# control_board-mixed.net
KiCad netlist of a schematic drawn in EAGLE
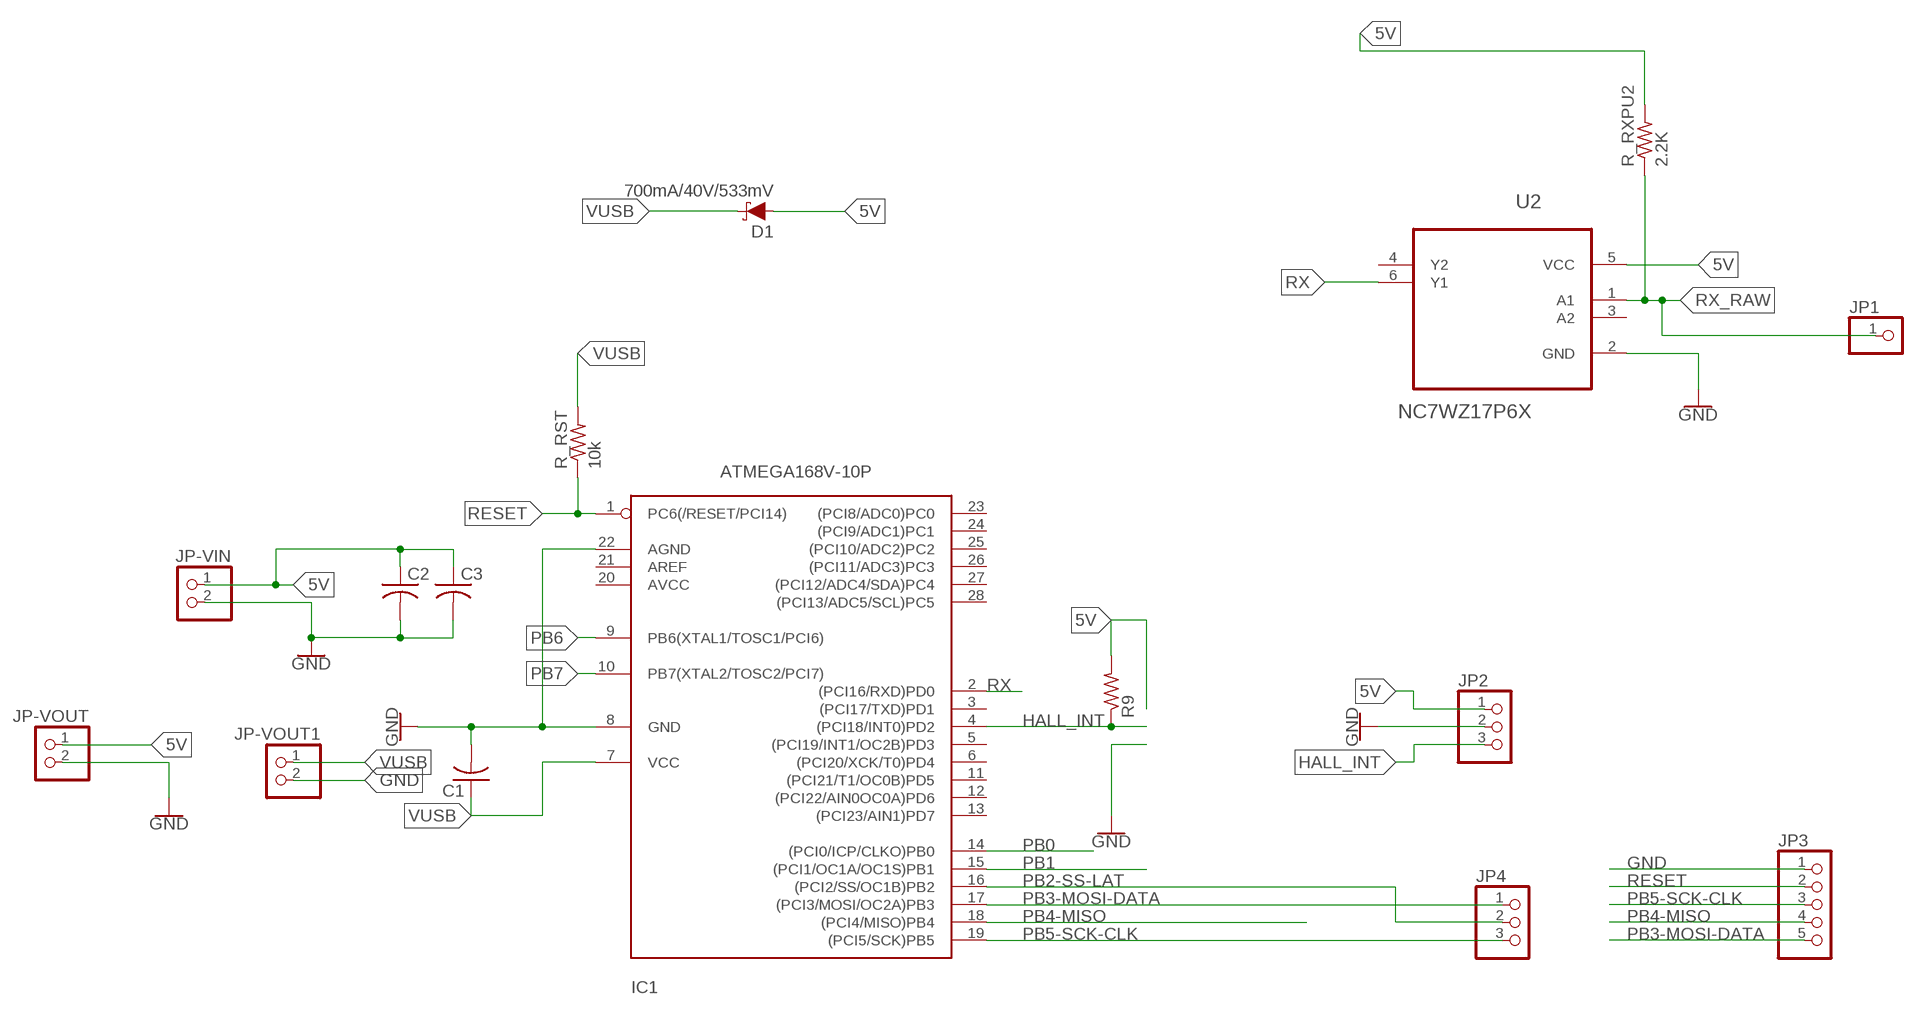
[diagram p0: schematic, sheet 1]

(export (version "E")
  (design (tool "Eeschema 10.0.6"))
  (components
    (comp (ref "C1")
      (value "C-US025-030X050")
      (footprint "eagle-import:C025-030X050")
      (libsource (lib "eagle-import") (part "C-US025-030X050"))
    )
    (comp (ref "C2")
      (value "C-US025-060X050")
      (footprint "eagle-import:C025-060X050")
      (libsource (lib "eagle-import") (part "C-US025-060X050"))
    )
    (comp (ref "C3")
      (value "C-US025-060X050")
      (footprint "eagle-import:C025-060X050")
      (libsource (lib "eagle-import") (part "C-US025-060X050"))
    )
    (comp (ref "D1")
      (value "700mA/40V/533mV")
      (footprint "eagle-import:SOT23-3")
      (libsource (lib "eagle-import") (part "DIODE-SCHOTTKY-ZLLS500"))
    )
    (comp (ref "IC1")
      (value "ATMEGA168V-10P")
      (footprint "eagle-import:DIL28-3")
      (libsource (lib "eagle-import") (part "ATMEGA168PV-10"))
    )
    (comp (ref "JP-VIN")
      (value "PINHD-1X2")
      (footprint "eagle-import:1X02")
      (libsource (lib "eagle-import") (part "PINHD-1X2"))
    )
    (comp (ref "JP-VOUT")
      (value "PINHD-1X2")
      (footprint "eagle-import:1X02")
      (libsource (lib "eagle-import") (part "PINHD-1X2"))
    )
    (comp (ref "JP-VOUT1")
      (value "PINHD-1X2")
      (footprint "eagle-import:1X02")
      (libsource (lib "eagle-import") (part "PINHD-1X2"))
    )
    (comp (ref "JP1")
      (value "PINHD-1X1")
      (footprint "eagle-import:1X01")
      (libsource (lib "eagle-import") (part "PINHD-1X1"))
    )
    (comp (ref "JP2")
      (value "PINHD-1X3")
      (footprint "eagle-import:1X03")
      (libsource (lib "eagle-import") (part "PINHD-1X3"))
    )
    (comp (ref "JP3")
      (value "PINHD-1X5")
      (footprint "eagle-import:1X05")
      (libsource (lib "eagle-import") (part "PINHD-1X5"))
    )
    (comp (ref "JP4")
      (value "PINHD-1X3")
      (footprint "eagle-import:1X03")
      (libsource (lib "eagle-import") (part "PINHD-1X3"))
    )
    (comp (ref "R9")
      (value "R-US_0207/7")
      (footprint "eagle-import:0207_7")
      (libsource (lib "eagle-import") (part "R-US_0207/7"))
    )
    (comp (ref "R_RST")
      (value "10k")
      (footprint "eagle-import:R0603")
      (libsource (lib "eagle-import") (part "R-US_R0603"))
    )
    (comp (ref "R_RXPU2")
      (value "2.2K")
      (footprint "eagle-import:R0603")
      (libsource (lib "eagle-import") (part "R-US_R0603"))
    )
    (comp (ref "U2")
      (value "NC7WZ17P6X")
      (footprint "eagle-import:SOT65P210X110-6N")
      (fields (field (name "MF") "Fairchild Semiconductor"))
      (libsource (lib "eagle-import") (part "NC7WZ17P6X"))
    )
  )
  (nets
    (net (code "1") (name "/PB0") (class "Default")
      (node (ref "IC1") (pin "14") (pinfunction "(PCI0/ICP/CLKO)PB0_14") (pintype "bidirectional"))
    )
    (net (code "2") (name "/PB1") (class "Default")
      (node (ref "IC1") (pin "15") (pinfunction "(PCI1/OC1A/OC1S)PB1_15") (pintype "bidirectional"))
    )
    (net (code "3") (name "/PB2-SS-LAT") (class "Default")
      (node (ref "IC1") (pin "16") (pinfunction "(PCI2/SS/OC1B)PB2_16") (pintype "bidirectional"))
      (node (ref "JP4") (pin "2") (pinfunction "2_2") (pintype "passive"))
    )
    (net (code "4") (name "/PB3-MOSI-DATA") (class "Default")
      (node (ref "IC1") (pin "17") (pinfunction "(PCI3/MOSI/OC2A)PB3_17") (pintype "bidirectional"))
      (node (ref "JP3") (pin "5") (pinfunction "5_5") (pintype "passive"))
      (node (ref "JP4") (pin "1") (pinfunction "1_1") (pintype "passive"))
    )
    (net (code "5") (name "/PB4-MISO") (class "Default")
      (node (ref "IC1") (pin "18") (pinfunction "(PCI4/MISO)PB4_18") (pintype "bidirectional"))
      (node (ref "JP3") (pin "4") (pinfunction "4_4") (pintype "passive"))
    )
    (net (code "6") (name "/PB5-SCK-CLK") (class "Default")
      (node (ref "IC1") (pin "19") (pinfunction "(PCI5/SCK)PB5_19") (pintype "bidirectional"))
      (node (ref "JP3") (pin "3") (pinfunction "3_3") (pintype "passive"))
      (node (ref "JP4") (pin "3") (pinfunction "3_3") (pintype "passive"))
    )
    (net (code "7") (name "5V") (class "Default")
      (node (ref "C2") (pin "1") (pinfunction "1_1") (pintype "passive"))
      (node (ref "C3") (pin "1") (pinfunction "1_1") (pintype "passive"))
      (node (ref "D1") (pin "1") (pinfunction "A_1") (pintype "passive"))
      (node (ref "JP-VIN") (pin "1") (pinfunction "1_1") (pintype "passive"))
      (node (ref "JP-VOUT") (pin "1") (pinfunction "1_1") (pintype "passive"))
      (node (ref "JP2") (pin "1") (pinfunction "1_1") (pintype "passive"))
      (node (ref "R9") (pin "2") (pinfunction "2_2") (pintype "passive"))
      (node (ref "R_RXPU2") (pin "2") (pinfunction "2_2") (pintype "passive"))
      (node (ref "U2") (pin "5") (pinfunction "VCC_5") (pintype "power_in"))
    )
    (net (code "8") (name "GND") (class "Default")
      (node (ref "C1") (pin "2") (pinfunction "2_2") (pintype "passive"))
      (node (ref "C2") (pin "2") (pinfunction "2_2") (pintype "passive"))
      (node (ref "C3") (pin "2") (pinfunction "2_2") (pintype "passive"))
      (node (ref "IC1") (pin "22") (pinfunction "AGND_22") (pintype "bidirectional"))
      (node (ref "IC1") (pin "8") (pinfunction "GND_8") (pintype "bidirectional"))
      (node (ref "JP-VIN") (pin "2") (pinfunction "2_2") (pintype "passive"))
      (node (ref "JP-VOUT") (pin "2") (pinfunction "2_2") (pintype "passive"))
      (node (ref "JP-VOUT1") (pin "2") (pinfunction "2_2") (pintype "passive"))
      (node (ref "JP2") (pin "2") (pinfunction "2_2") (pintype "passive"))
      (node (ref "JP3") (pin "1") (pinfunction "1_1") (pintype "passive"))
      (node (ref "U2") (pin "2") (pinfunction "GND_2") (pintype "passive"))
    )
    (net (code "9") (name "HALL_INT") (class "Default")
      (node (ref "IC1") (pin "4") (pinfunction "(PCI18/INT0)PD2_4") (pintype "bidirectional"))
      (node (ref "JP2") (pin "3") (pinfunction "3_3") (pintype "passive"))
      (node (ref "R9") (pin "1") (pinfunction "1_1") (pintype "passive"))
    )
    (net (code "10") (name "PB6") (class "Default")
      (node (ref "IC1") (pin "9") (pinfunction "PB6(XTAL1/TOSC1/PCI6)_9") (pintype "bidirectional"))
    )
    (net (code "11") (name "PB7") (class "Default")
      (node (ref "IC1") (pin "10") (pinfunction "PB7(XTAL2/TOSC2/PCI7)_10") (pintype "bidirectional"))
    )
    (net (code "12") (name "RESET") (class "Default")
      (node (ref "IC1") (pin "1") (pinfunction "PC6(/RESET/PCI14)_1") (pintype "bidirectional"))
      (node (ref "JP3") (pin "2") (pinfunction "2_2") (pintype "passive"))
      (node (ref "R_RST") (pin "1") (pinfunction "1_1") (pintype "passive"))
    )
    (net (code "13") (name "RX") (class "Default")
      (node (ref "IC1") (pin "2") (pinfunction "(PCI16/RXD)PD0_2") (pintype "bidirectional"))
      (node (ref "U2") (pin "6") (pinfunction "Y1_6") (pintype "output"))
    )
    (net (code "14") (name "RX_RAW") (class "Default")
      (node (ref "JP1") (pin "1") (pinfunction "1_1") (pintype "passive"))
      (node (ref "R_RXPU2") (pin "1") (pinfunction "1_1") (pintype "passive"))
      (node (ref "U2") (pin "1") (pinfunction "A1_1") (pintype "input"))
    )
    (net (code "15") (name "VUSB") (class "Default")
      (node (ref "C1") (pin "1") (pinfunction "1_1") (pintype "passive"))
      (node (ref "D1") (pin "3") (pinfunction "C_3") (pintype "passive"))
      (node (ref "IC1") (pin "7") (pinfunction "VCC_7") (pintype "bidirectional"))
      (node (ref "JP-VOUT1") (pin "1") (pinfunction "1_1") (pintype "passive"))
      (node (ref "R_RST") (pin "2") (pinfunction "2_2") (pintype "passive"))
    )
    (net (code "16") (name "unconnected-(IC1-(PCI8{slash}ADC0)PC0-Pad23)") (class "Default")
      (node (ref "IC1") (pin "23") (pinfunction "(PCI8/ADC0)PC0_23") (pintype "bidirectional"))
    )
    (net (code "17") (name "unconnected-(IC1-(PCI9{slash}ADC1)PC1-Pad24)") (class "Default")
      (node (ref "IC1") (pin "24") (pinfunction "(PCI9/ADC1)PC1_24") (pintype "bidirectional"))
    )
    (net (code "18") (name "unconnected-(IC1-(PCI10{slash}ADC2)PC2-Pad25)") (class "Default")
      (node (ref "IC1") (pin "25") (pinfunction "(PCI10/ADC2)PC2_25") (pintype "bidirectional"))
    )
    (net (code "19") (name "unconnected-(IC1-(PCI11{slash}ADC3)PC3-Pad26)") (class "Default")
      (node (ref "IC1") (pin "26") (pinfunction "(PCI11/ADC3)PC3_26") (pintype "bidirectional"))
    )
    (net (code "20") (name "unconnected-(IC1-(PCI12{slash}ADC4{slash}SDA)PC4-Pad27)") (class "Default")
      (node (ref "IC1") (pin "27") (pinfunction "(PCI12/ADC4/SDA)PC4_27") (pintype "bidirectional"))
    )
    (net (code "21") (name "unconnected-(IC1-(PCI13{slash}ADC5{slash}SCL)PC5-Pad28)") (class "Default")
      (node (ref "IC1") (pin "28") (pinfunction "(PCI13/ADC5/SCL)PC5_28") (pintype "bidirectional"))
    )
    (net (code "22") (name "unconnected-(IC1-(PCI17{slash}TXD)PD1-Pad3)") (class "Default")
      (node (ref "IC1") (pin "3") (pinfunction "(PCI17/TXD)PD1_3") (pintype "bidirectional"))
    )
    (net (code "23") (name "unconnected-(IC1-(PCI19{slash}INT1{slash}OC2B)PD3-Pad5)") (class "Default")
      (node (ref "IC1") (pin "5") (pinfunction "(PCI19/INT1/OC2B)PD3_5") (pintype "bidirectional"))
    )
    (net (code "24") (name "unconnected-(IC1-(PCI20{slash}XCK{slash}T0)PD4-Pad6)") (class "Default")
      (node (ref "IC1") (pin "6") (pinfunction "(PCI20/XCK/T0)PD4_6") (pintype "bidirectional"))
    )
    (net (code "25") (name "unconnected-(IC1-(PCI21{slash}T1{slash}OC0B)PD5-Pad11)") (class "Default")
      (node (ref "IC1") (pin "11") (pinfunction "(PCI21/T1/OC0B)PD5_11") (pintype "bidirectional"))
    )
    (net (code "26") (name "unconnected-(IC1-(PCI22{slash}AIN0OC0A)PD6-Pad12)") (class "Default")
      (node (ref "IC1") (pin "12") (pinfunction "(PCI22/AIN0OC0A)PD6_12") (pintype "bidirectional"))
    )
    (net (code "27") (name "unconnected-(IC1-(PCI23{slash}AIN1)PD7-Pad13)") (class "Default")
      (node (ref "IC1") (pin "13") (pinfunction "(PCI23/AIN1)PD7_13") (pintype "bidirectional"))
    )
    (net (code "28") (name "unconnected-(IC1-AREF-Pad21)") (class "Default")
      (node (ref "IC1") (pin "21") (pinfunction "AREF_21") (pintype "bidirectional"))
    )
    (net (code "29") (name "unconnected-(IC1-AVCC-Pad20)") (class "Default")
      (node (ref "IC1") (pin "20") (pinfunction "AVCC_20") (pintype "bidirectional"))
    )
    (net (code "30") (name "unconnected-(U2-A2-Pad3)") (class "Default")
      (node (ref "U2") (pin "3") (pinfunction "A2_3") (pintype "input"))
    )
    (net (code "31") (name "unconnected-(U2-Y2-Pad4)") (class "Default")
      (node (ref "U2") (pin "4") (pinfunction "Y2_4") (pintype "output"))
    )
  )
)
